# 3_DotexBoard_Interfaces.net
KiCad netlist of a schematic drawn in Altium Designer
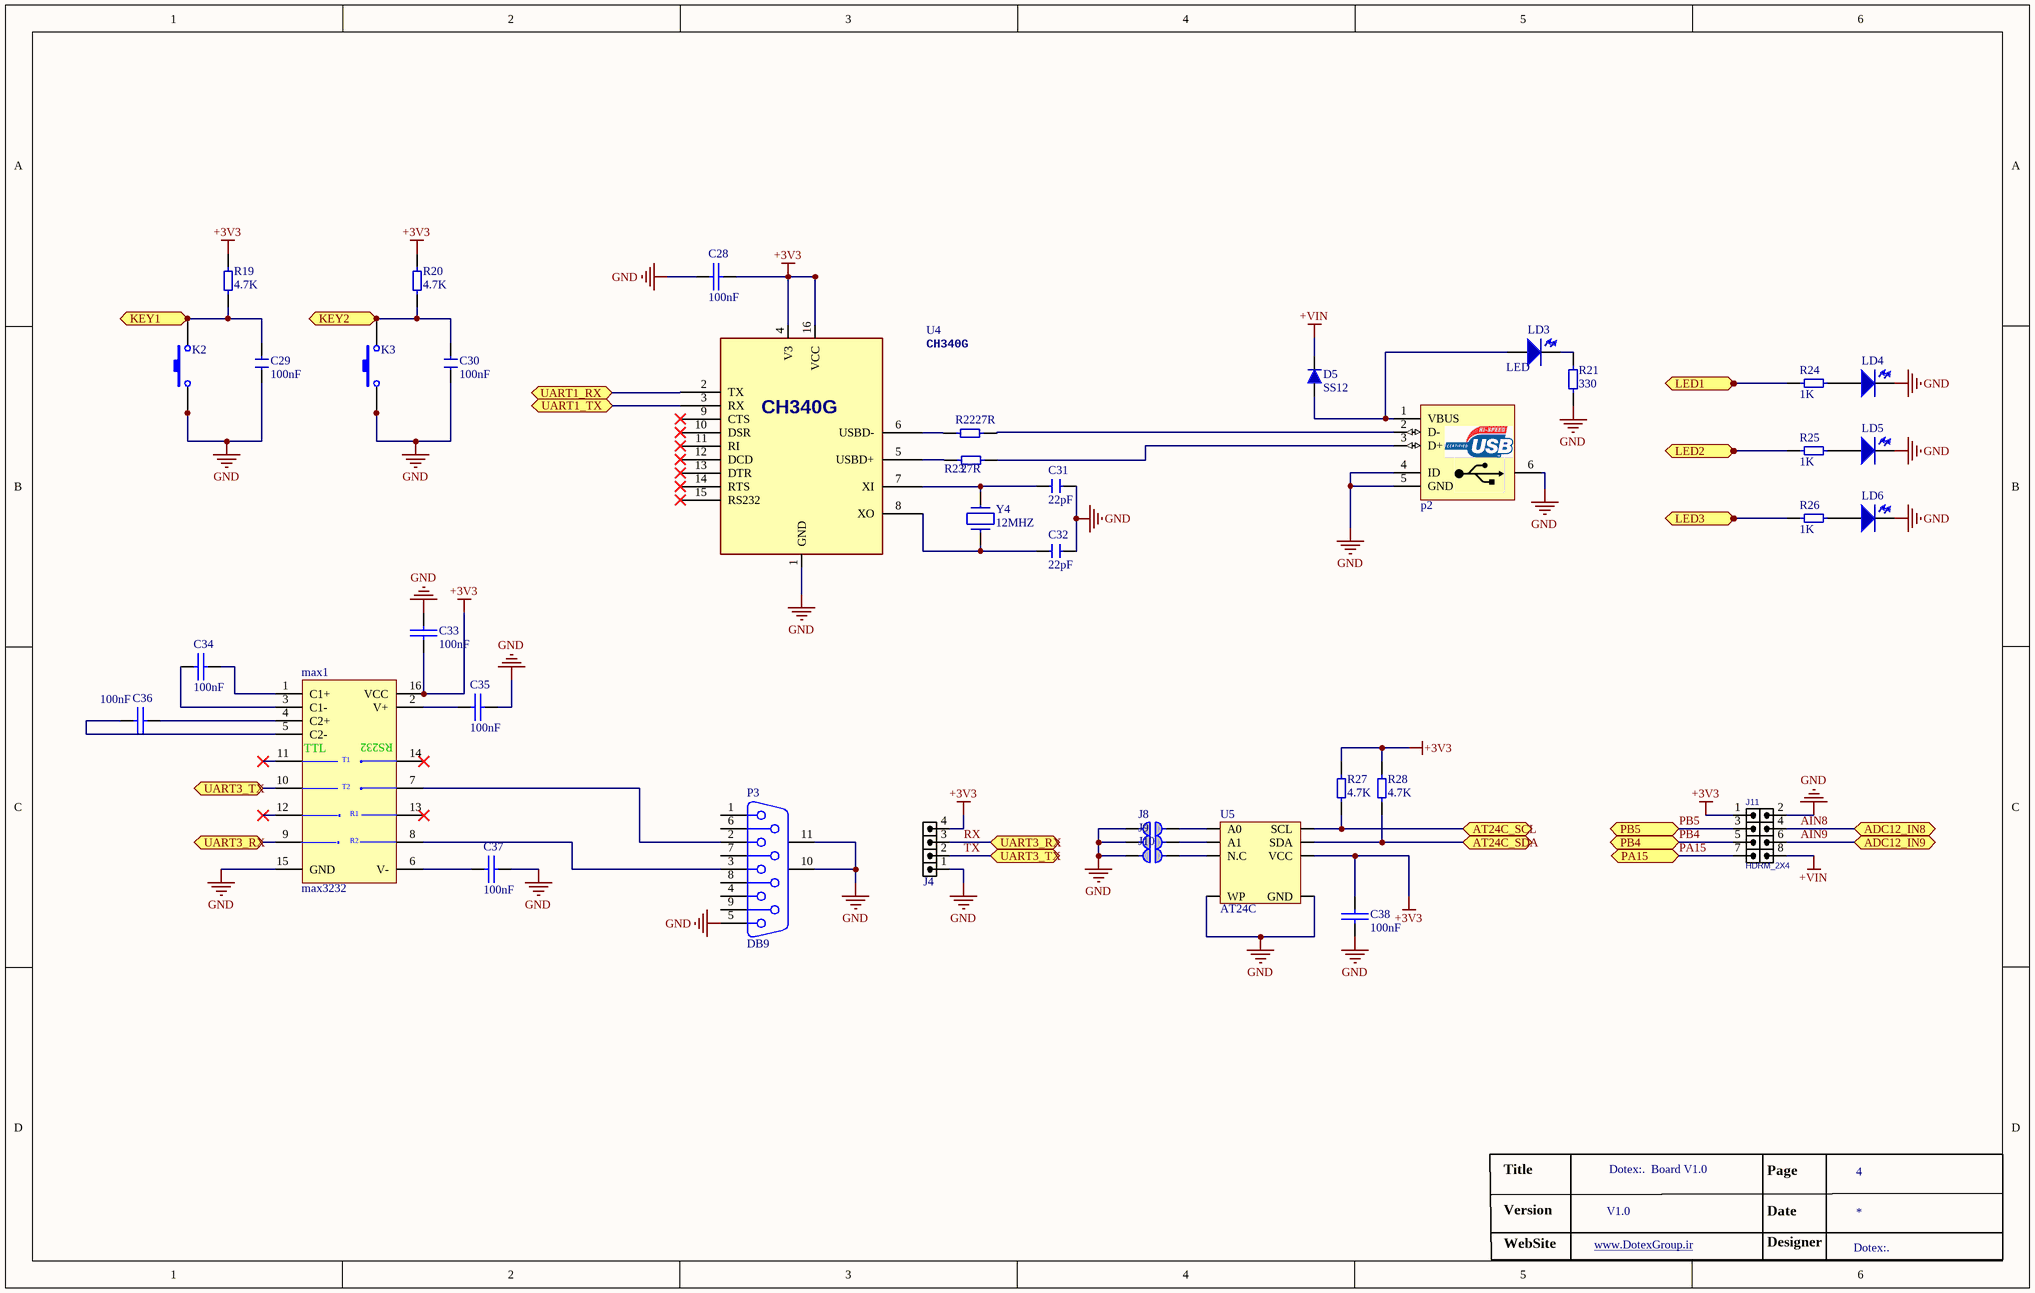
[diagram p0: [3]DotexBoard_Interfaces.SchDoc]

(export (version "E")
  (design (tool "Eeschema 10.0.6"))
  (components
    (comp (ref "C28")
      (value "100nF")
      (footprint "0805 Capacitor")
      (description "Bipolar Capacitor")
      (fields
        (field (name "VOLTAGE") "100V")
        (field (name "Comment") "Comment")
        (field (name "DESIGNER") "Saeid Jorablo")
      )
      (libsource (lib "DotexGroup_LIB") (part "Cap-Bipolar"))
    )
    (comp (ref "C29")
      (value "Comment")
      (footprint "0805 Capacitor")
      (fields (field (name "ALTIUM_UNNAMED_1") "100nF"))
      (libsource (lib "DotexGroup_LIB") (part "Capacitor SMD"))
    )
    (comp (ref "C30")
      (value "Comment")
      (footprint "0805 Capacitor")
      (fields (field (name "ALTIUM_UNNAMED_1") "100nF"))
      (libsource (lib "DotexGroup_LIB") (part "Capacitor SMD"))
    )
    (comp (ref "C31")
      (value "Comment")
      (footprint "0805 Capacitor")
      (fields (field (name "ALTIUM_UNNAMED_1") "22pF"))
      (libsource (lib "DotexGroup_LIB") (part "Capacitor SMD"))
    )
    (comp (ref "C32")
      (value "Comment")
      (footprint "0805 Capacitor")
      (fields (field (name "ALTIUM_UNNAMED_1") "22pF"))
      (libsource (lib "DotexGroup_LIB") (part "Capacitor SMD"))
    )
    (comp (ref "C33")
      (value "100nF")
      (footprint "0805 Capacitor")
      (description "Bipolar Capacitor")
      (fields
        (field (name "VOLTAGE") "100V")
        (field (name "Comment") "Comment")
        (field (name "DESIGNER") "Saeid Jorablo")
      )
      (libsource (lib "DotexGroup_LIB") (part "Cap-Bipolar"))
    )
    (comp (ref "C34")
      (value "100nF")
      (footprint "0805 Capacitor")
      (description "Bipolar Capacitor")
      (fields
        (field (name "VOLTAGE") "100V")
        (field (name "Comment") "Comment")
        (field (name "DESIGNER") "Saeid Jorablo")
      )
      (libsource (lib "DotexGroup_LIB") (part "Cap-Bipolar"))
    )
    (comp (ref "C35")
      (value "100nF")
      (footprint "0805 Capacitor")
      (description "Bipolar Capacitor")
      (fields
        (field (name "VOLTAGE") "100V")
        (field (name "Comment") "Comment")
        (field (name "DESIGNER") "Saeid Jorablo")
      )
      (libsource (lib "DotexGroup_LIB") (part "Cap-Bipolar"))
    )
    (comp (ref "C36")
      (value "100nF")
      (footprint "0805 Capacitor")
      (description "Bipolar Capacitor")
      (fields
        (field (name "VOLTAGE") "100V")
        (field (name "Comment") "Comment")
        (field (name "DESIGNER") "Saeid Jorablo")
      )
      (libsource (lib "") (part "Cap-Bipolar_1"))
    )
    (comp (ref "C37")
      (value "100nF")
      (footprint "0805 Capacitor")
      (description "Bipolar Capacitor")
      (fields
        (field (name "VOLTAGE") "100V")
        (field (name "Comment") "Comment")
        (field (name "DESIGNER") "Saeid Jorablo")
      )
      (libsource (lib "") (part "Cap-Bipolar_1"))
    )
    (comp (ref "C38")
      (value "100nF")
      (footprint "0805 Capacitor")
      (description "Bipolar Capacitor")
      (fields
        (field (name "VOLTAGE") "100V")
        (field (name "Comment") "Comment")
        (field (name "DESIGNER") "Saeid Jorablo")
      )
      (libsource (lib "") (part "Cap-Bipolar_1"))
    )
    (comp (ref "D5")
      (value "SS12")
      (footprint "DO-214AC(SMA)")
      (libsource (lib "DotexGroup_LIB") (part "1N4001"))
    )
    (comp (ref "J4")
      (value "HDR1X4")
      (footprint "HDR_M_1X4")
      (description "CONN, HEADER, Male, pitch: 2.54mm, 4POS")
      (libsource (lib "DotexGroup_LIB") (part "HDR_M_1X4"))
    )
    (comp (ref "J8")
      (value "Comment")
      (footprint "0603 Resistor")
      (libsource (lib "DotexGroup_LIB") (part "jumper SMD"))
    )
    (comp (ref "J9")
      (value "Comment")
      (footprint "0603 Resistor")
      (libsource (lib "DotexGroup_LIB") (part "jumper SMD"))
    )
    (comp (ref "J10")
      (value "Comment")
      (footprint "0603 Resistor")
      (libsource (lib "DotexGroup_LIB") (part "jumper SMD"))
    )
    (comp (ref "J11")
      (value "HDRM_2X4")
      (footprint "HDR_M_2X4")
      (description "CONN, HEADER, Male, pitch: 2.54mm, 8POS")
      (fields (field (name "MANF_P#") "MANF_PART#") (field (name "MANF") "MANF"))
      (libsource (lib "DotexGroup_LIB") (part "HDR_M_2X4"))
    )
    (comp (ref "K2")
      (value "Comment")
      (footprint "Push Kay 4 KFC")
      (libsource (lib "DotexGroup_LIB") (part "Push Kay"))
    )
    (comp (ref "K3")
      (value "Comment")
      (footprint "Push Kay 4 KFC")
      (libsource (lib "DotexGroup_LIB") (part "Push Kay"))
    )
    (comp (ref "LD3")
      (value "LED")
      (footprint "LED_0805 Y")
      (libsource (lib "DotexGroup_LIB") (part "LED SMD"))
    )
    (comp (ref "LD4")
      (value "Comment")
      (footprint "LED_0805 Y")
      (libsource (lib "DotexGroup_LIB") (part "LED SMD"))
    )
    (comp (ref "LD5")
      (value "Comment")
      (footprint "LED_0805 Y")
      (libsource (lib "DotexGroup_LIB") (part "LED SMD"))
    )
    (comp (ref "LD6")
      (value "Comment")
      (footprint "LED_0805 Y")
      (libsource (lib "DotexGroup_LIB") (part "LED SMD"))
    )
    (comp (ref "max1")
      (value "max3232")
      (footprint "SO-16")
      (description "+5V Powered, Multi-Channel RS-232 Driver/Receiver")
      (fields (field (name "COMPONENTAUTHOR") "Saeid Jorablo"))
      (libsource (lib "DotexGroup_LIB") (part "MAX232"))
    )
    (comp (ref "p2")
      (value "USB Connector")
      (footprint "USB_AB_BM_SHS")
      (description "USB MICRO-B Type Connector")
      (fields (field (name "DESIGNER") "ABBAS BASEREH") (field (name "PUBLISHER") "ABBAS BASEREH"))
      (libsource (lib "DotexGroup_LIB") (part "USB AB MICRO CONNECTOR"))
    )
    (comp (ref "P3")
      (value "DB9")
      (footprint "DB9 Female")
      (description "Receptacle Assembly, 9 Position, Right Angle")
      (fields (field (name "PUBLISHER") "Altium Limited"))
      (libsource (lib "DotexGroup_LIB") (part "DB9 Connector"))
    )
    (comp (ref "R19")
      (value "Comment")
      (footprint "0805 Resistor")
      (fields (field (name "ALTIUM_UNNAMED_1") "4.7K"))
      (libsource (lib "DotexGroup_LIB") (part "Resistor SMD"))
    )
    (comp (ref "R20")
      (value "Comment")
      (footprint "0805 Resistor")
      (fields (field (name "ALTIUM_UNNAMED_1") "4.7K"))
      (libsource (lib "DotexGroup_LIB") (part "Resistor SMD"))
    )
    (comp (ref "R21")
      (value "Comment")
      (footprint "0805 Resistor")
      (fields (field (name "ALTIUM_UNNAMED_1") "330"))
      (libsource (lib "DotexGroup_LIB") (part "Resistor SMD"))
    )
    (comp (ref "R22")
      (value "Comment")
      (footprint "0805 Resistor")
      (fields (field (name "ALTIUM_UNNAMED_1") "27R"))
      (libsource (lib "DotexGroup_LIB") (part "Resistor SMD"))
    )
    (comp (ref "R23")
      (value "Comment")
      (footprint "0805 Resistor")
      (fields (field (name "ALTIUM_UNNAMED_1") "27R"))
      (libsource (lib "DotexGroup_LIB") (part "Resistor SMD"))
    )
    (comp (ref "R24")
      (value "Comment")
      (footprint "0805 Resistor")
      (fields (field (name "ALTIUM_UNNAMED_1") "1K"))
      (libsource (lib "DotexGroup_LIB") (part "Resistor SMD"))
    )
    (comp (ref "R25")
      (value "Comment")
      (footprint "0805 Resistor")
      (fields (field (name "ALTIUM_UNNAMED_1") "1K"))
      (libsource (lib "DotexGroup_LIB") (part "Resistor SMD"))
    )
    (comp (ref "R26")
      (value "Comment")
      (footprint "0805 Resistor")
      (fields (field (name "ALTIUM_UNNAMED_1") "1K"))
      (libsource (lib "DotexGroup_LIB") (part "Resistor SMD"))
    )
    (comp (ref "R27")
      (value "Comment")
      (footprint "0805 Resistor")
      (fields (field (name "ALTIUM_UNNAMED_1") "4.7K"))
      (libsource (lib "DotexGroup_LIB") (part "Resistor SMD"))
    )
    (comp (ref "R28")
      (value "Comment")
      (footprint "0805 Resistor")
      (fields (field (name "ALTIUM_UNNAMED_1") "4.7K"))
      (libsource (lib "DotexGroup_LIB") (part "Resistor SMD"))
    )
    (comp (ref "U4")
      (value "CH340G")
      (footprint "SO-16")
      (description "USB-UART")
      (libsource (lib "DotexGroup_LIB") (part "CH340G_SOP16"))
    )
    (comp (ref "U5")
      (value "AT24C")
      (footprint "SOIC-8")
      (libsource (lib "DotexGroup_LIB") (part "AT24C128"))
    )
    (comp (ref "Y4") (value "12MHZ") (footprint "Xtal 2p") (libsource (lib "DotexGroup_LIB") (part "Xtal")))
  )
  (nets
    (net (code "1") (name "+3V3") (class "Default")
      (node (ref "C28") (pin "2") (pinfunction "-_2") (pintype "passive"))
      (node (ref "C33") (pin "1") (pinfunction "+_1") (pintype "passive"))
      (node (ref "C38") (pin "1") (pinfunction "+_1") (pintype "passive"))
      (node (ref "J11") (pin "1") (pinfunction "1_1") (pintype "passive"))
      (node (ref "J4") (pin "4") (pinfunction "4_4") (pintype "passive"))
      (node (ref "R19") (pin "1") (pintype "passive"))
      (node (ref "R20") (pin "1") (pintype "passive"))
      (node (ref "R27") (pin "1") (pintype "passive"))
      (node (ref "R28") (pin "1") (pintype "passive"))
      (node (ref "U4") (pin "16") (pinfunction "VCC_16") (pintype "passive"))
      (node (ref "U4") (pin "4") (pinfunction "V3_4") (pintype "passive"))
      (node (ref "U5") (pin "8") (pinfunction "VCC_8") (pintype "passive"))
      (node (ref "max1") (pin "16") (pinfunction "VCC_16") (pintype "power_in"))
    )
    (net (code "2") (name "+VIN") (class "Default")
      (node (ref "D5") (pin "2") (pinfunction "K_2") (pintype "passive"))
      (node (ref "J11") (pin "8") (pinfunction "8_8") (pintype "passive"))
    )
    (net (code "3") (name "/AIN8") (class "Default")
      (node (ref "J11") (pin "4") (pinfunction "4_4") (pintype "passive"))
    )
    (net (code "4") (name "/AIN9") (class "Default")
      (node (ref "J11") (pin "6") (pinfunction "6_6") (pintype "passive"))
    )
    (net (code "5") (name "/AT24C_SCL") (class "Default")
      (node (ref "R27") (pin "2") (pintype "passive"))
      (node (ref "U5") (pin "6") (pinfunction "SCL_6") (pintype "passive"))
    )
    (net (code "6") (name "/AT24C_SDA") (class "Default")
      (node (ref "R28") (pin "2") (pintype "passive"))
      (node (ref "U5") (pin "5") (pinfunction "SDA_5") (pintype "passive"))
    )
    (net (code "7") (name "/KEY1") (class "Default")
      (node (ref "C29") (pin "1") (pintype "passive"))
      (node (ref "K2") (pin "2") (pinfunction "2_2") (pintype "passive"))
      (node (ref "R19") (pin "2") (pintype "passive"))
    )
    (net (code "8") (name "/KEY2") (class "Default")
      (node (ref "C30") (pin "1") (pintype "passive"))
      (node (ref "K3") (pin "2") (pinfunction "2_2") (pintype "passive"))
      (node (ref "R20") (pin "2") (pintype "passive"))
    )
    (net (code "9") (name "/LED1") (class "Default") (node (ref "R24") (pin "1") (pintype "passive")))
    (net (code "10") (name "/LED2") (class "Default") (node (ref "R25") (pin "1") (pintype "passive")))
    (net (code "11") (name "/LED3") (class "Default") (node (ref "R26") (pin "1") (pintype "passive")))
    (net (code "12") (name "/PA15") (class "Default")
      (node (ref "J11") (pin "7") (pinfunction "7_7") (pintype "passive"))
    )
    (net (code "13") (name "/PB4") (class "Default")
      (node (ref "J11") (pin "5") (pinfunction "5_5") (pintype "passive"))
    )
    (net (code "14") (name "/PB5") (class "Default")
      (node (ref "J11") (pin "3") (pinfunction "3_3") (pintype "passive"))
    )
    (net (code "15") (name "/RX") (class "Default")
      (node (ref "J4") (pin "3") (pinfunction "3_3") (pintype "passive"))
      (node (ref "max1") (pin "9") (pinfunction "R2OUT_9") (pintype "passive"))
    )
    (net (code "16") (name "/TX") (class "Default")
      (node (ref "J4") (pin "2") (pinfunction "2_2") (pintype "passive"))
      (node (ref "max1") (pin "10") (pinfunction "T2IN_10") (pintype "passive"))
    )
    (net (code "17") (name "/UART1_RX") (class "Default")
      (node (ref "U4") (pin "2") (pinfunction "TX_2") (pintype "passive"))
    )
    (net (code "18") (name "/UART1_TX") (class "Default")
      (node (ref "U4") (pin "3") (pinfunction "RX_3") (pintype "passive"))
    )
    (net (code "19") (name "GND") (class "Default")
      (node (ref "C28") (pin "1") (pinfunction "+_1") (pintype "passive"))
      (node (ref "C29") (pin "2") (pintype "passive"))
      (node (ref "C30") (pin "2") (pintype "passive"))
      (node (ref "C31") (pin "1") (pintype "passive"))
      (node (ref "C32") (pin "2") (pintype "passive"))
      (node (ref "C33") (pin "2") (pinfunction "-_2") (pintype "passive"))
      (node (ref "C35") (pin "2") (pinfunction "-_2") (pintype "passive"))
      (node (ref "C37") (pin "2") (pinfunction "-_2") (pintype "passive"))
      (node (ref "C38") (pin "2") (pinfunction "-_2") (pintype "passive"))
      (node (ref "J10") (pin "1") (pintype "passive"))
      (node (ref "J11") (pin "2") (pinfunction "2_2") (pintype "passive"))
      (node (ref "J4") (pin "1") (pinfunction "1_1") (pintype "passive"))
      (node (ref "J8") (pin "1") (pintype "passive"))
      (node (ref "J9") (pin "1") (pintype "passive"))
      (node (ref "K2") (pin "1") (pinfunction "1_1") (pintype "passive"))
      (node (ref "K3") (pin "1") (pinfunction "1_1") (pintype "passive"))
      (node (ref "LD4") (pin "2") (pinfunction "K_2") (pintype "passive"))
      (node (ref "LD5") (pin "2") (pinfunction "K_2") (pintype "passive"))
      (node (ref "LD6") (pin "2") (pinfunction "K_2") (pintype "passive"))
      (node (ref "P3") (pin "10") (pinfunction "MH1_10") (pintype "passive"))
      (node (ref "P3") (pin "11") (pinfunction "MH2_11") (pintype "passive"))
      (node (ref "P3") (pin "5") (pinfunction "5_5") (pintype "passive"))
      (node (ref "R21") (pin "2") (pintype "passive"))
      (node (ref "U4") (pin "1") (pinfunction "GND_1") (pintype "passive"))
      (node (ref "U5") (pin "4") (pinfunction "GND_4") (pintype "passive"))
      (node (ref "U5") (pin "7") (pinfunction "WP_7") (pintype "passive"))
      (node (ref "max1") (pin "15") (pinfunction "GND_15") (pintype "power_in"))
      (node (ref "p2") (pin "4") (pinfunction "ID_4") (pintype "power_in"))
      (node (ref "p2") (pin "5") (pinfunction "GND_5") (pintype "power_in"))
      (node (ref "p2") (pin "6") (pinfunction "MH_6") (pintype "power_in"))
    )
    (net (code "20") (name "Net-(C34-+)") (class "Default")
      (node (ref "C34") (pin "1") (pinfunction "+_1") (pintype "passive"))
      (node (ref "max1") (pin "1") (pinfunction "C1+_1") (pintype "passive"))
    )
    (net (code "21") (name "Net-(C34--)") (class "Default")
      (node (ref "C34") (pin "2") (pinfunction "-_2") (pintype "passive"))
      (node (ref "max1") (pin "3") (pinfunction "C1-_3") (pintype "passive"))
    )
    (net (code "22") (name "Net-(C35-+)") (class "Default")
      (node (ref "C35") (pin "1") (pinfunction "+_1") (pintype "passive"))
      (node (ref "max1") (pin "2") (pinfunction "V+_2") (pintype "passive"))
    )
    (net (code "23") (name "Net-(C36-+)") (class "Default")
      (node (ref "C36") (pin "1") (pinfunction "+_1") (pintype "passive"))
      (node (ref "max1") (pin "5") (pinfunction "C2-_5") (pintype "passive"))
    )
    (net (code "24") (name "Net-(C36--)") (class "Default")
      (node (ref "C36") (pin "2") (pinfunction "-_2") (pintype "passive"))
      (node (ref "max1") (pin "4") (pinfunction "C2+_4") (pintype "passive"))
    )
    (net (code "25") (name "Net-(C37-+)") (class "Default")
      (node (ref "C37") (pin "1") (pinfunction "+_1") (pintype "passive"))
      (node (ref "max1") (pin "6") (pinfunction "V-_6") (pintype "passive"))
    )
    (net (code "26") (name "Net-(D5-A)") (class "Default")
      (node (ref "D5") (pin "1") (pinfunction "A_1") (pintype "passive"))
      (node (ref "LD3") (pin "1") (pinfunction "A_1") (pintype "passive"))
      (node (ref "p2") (pin "1") (pinfunction "VBUS_1") (pintype "power_in"))
    )
    (net (code "27") (name "Net-(LD3-K)") (class "Default")
      (node (ref "LD3") (pin "2") (pinfunction "K_2") (pintype "passive"))
      (node (ref "R21") (pin "1") (pintype "passive"))
    )
    (net (code "28") (name "Net-(LD4-A)") (class "Default")
      (node (ref "LD4") (pin "1") (pinfunction "A_1") (pintype "passive"))
      (node (ref "R24") (pin "2") (pintype "passive"))
    )
    (net (code "29") (name "Net-(LD5-A)") (class "Default")
      (node (ref "LD5") (pin "1") (pinfunction "A_1") (pintype "passive"))
      (node (ref "R25") (pin "2") (pintype "passive"))
    )
    (net (code "30") (name "Net-(LD6-A)") (class "Default")
      (node (ref "LD6") (pin "1") (pinfunction "A_1") (pintype "passive"))
      (node (ref "R26") (pin "2") (pintype "passive"))
    )
    (net (code "31") (name "Net-(U4-USBD+)") (class "Default")
      (node (ref "R23") (pin "1") (pintype "passive"))
      (node (ref "U4") (pin "5") (pinfunction "USBD+_5") (pintype "passive"))
    )
    (net (code "32") (name "Net-(U4-USBD-)") (class "Default")
      (node (ref "R22") (pin "1") (pintype "passive"))
      (node (ref "U4") (pin "6") (pinfunction "USBD-_6") (pintype "passive"))
    )
    (net (code "33") (name "Net-(U4-XI)") (class "Default")
      (node (ref "C31") (pin "2") (pintype "passive"))
      (node (ref "U4") (pin "7") (pinfunction "XI_7") (pintype "passive"))
      (node (ref "Y4") (pin "2") (pintype "passive"))
    )
    (net (code "34") (name "Net-(U4-XO)") (class "Default")
      (node (ref "C32") (pin "1") (pintype "passive"))
      (node (ref "U4") (pin "8") (pinfunction "XO_8") (pintype "passive"))
      (node (ref "Y4") (pin "1") (pintype "passive"))
    )
    (net (code "35") (name "Net-(U5-A0)") (class "Default")
      (node (ref "J8") (pin "2") (pintype "passive"))
      (node (ref "U5") (pin "1") (pinfunction "A0_1") (pintype "passive"))
    )
    (net (code "36") (name "Net-(U5-A1)") (class "Default")
      (node (ref "J9") (pin "2") (pintype "passive"))
      (node (ref "U5") (pin "2") (pinfunction "A1_2") (pintype "passive"))
    )
    (net (code "37") (name "Net-(U5-N.C)") (class "Default")
      (node (ref "J10") (pin "2") (pintype "passive"))
      (node (ref "U5") (pin "3") (pinfunction "N.C_3") (pintype "passive"))
    )
    (net (code "38") (name "Net-(max1-R2IN)") (class "Default")
      (node (ref "P3") (pin "3") (pinfunction "3_3") (pintype "passive"))
      (node (ref "max1") (pin "8") (pinfunction "R2IN_8") (pintype "passive"))
    )
    (net (code "39") (name "Net-(max1-T2OUT)") (class "Default")
      (node (ref "P3") (pin "2") (pinfunction "2_2") (pintype "passive"))
      (node (ref "max1") (pin "7") (pinfunction "T2OUT_7") (pintype "passive"))
    )
    (net (code "40") (name "Net-(p2-D+)") (class "Default")
      (node (ref "R23") (pin "2") (pintype "passive"))
      (node (ref "p2") (pin "3") (pinfunction "D+_3") (pintype "bidirectional"))
    )
    (net (code "41") (name "Net-(p2-D-)") (class "Default")
      (node (ref "R22") (pin "2") (pintype "passive"))
      (node (ref "p2") (pin "2") (pinfunction "D-_2") (pintype "bidirectional"))
    )
    (net (code "42") (name "unconnected-(P3-Pad1)") (class "Default")
      (node (ref "P3") (pin "1") (pinfunction "1_1") (pintype "passive"))
    )
    (net (code "43") (name "unconnected-(P3-Pad4)") (class "Default")
      (node (ref "P3") (pin "4") (pinfunction "4_4") (pintype "passive"))
    )
    (net (code "44") (name "unconnected-(P3-Pad6)") (class "Default")
      (node (ref "P3") (pin "6") (pinfunction "6_6") (pintype "passive"))
    )
    (net (code "45") (name "unconnected-(P3-Pad7)") (class "Default")
      (node (ref "P3") (pin "7") (pinfunction "7_7") (pintype "passive"))
    )
    (net (code "46") (name "unconnected-(P3-Pad8)") (class "Default")
      (node (ref "P3") (pin "8") (pinfunction "8_8") (pintype "passive"))
    )
    (net (code "47") (name "unconnected-(P3-Pad9)") (class "Default")
      (node (ref "P3") (pin "9") (pinfunction "9_9") (pintype "passive"))
    )
    (net (code "48") (name "unconnected-(U4-CTS-Pad9)") (class "Default")
      (node (ref "U4") (pin "9") (pinfunction "CTS_9") (pintype "passive+no_connect"))
    )
    (net (code "49") (name "unconnected-(U4-DCD-Pad12)") (class "Default")
      (node (ref "U4") (pin "12") (pinfunction "DCD_12") (pintype "passive+no_connect"))
    )
    (net (code "50") (name "unconnected-(U4-DSR-Pad10)") (class "Default")
      (node (ref "U4") (pin "10") (pinfunction "DSR_10") (pintype "passive+no_connect"))
    )
    (net (code "51") (name "unconnected-(U4-DTR-Pad13)") (class "Default")
      (node (ref "U4") (pin "13") (pinfunction "DTR_13") (pintype "passive+no_connect"))
    )
    (net (code "52") (name "unconnected-(U4-RI-Pad11)") (class "Default")
      (node (ref "U4") (pin "11") (pinfunction "RI_11") (pintype "passive+no_connect"))
    )
    (net (code "53") (name "unconnected-(U4-RS232-Pad15)") (class "Default")
      (node (ref "U4") (pin "15") (pinfunction "RS232_15") (pintype "passive+no_connect"))
    )
    (net (code "54") (name "unconnected-(U4-RTS-Pad14)") (class "Default")
      (node (ref "U4") (pin "14") (pinfunction "RTS_14") (pintype "passive+no_connect"))
    )
    (net (code "55") (name "unconnected-(max1-R1IN-Pad13)") (class "Default")
      (node (ref "max1") (pin "13") (pinfunction "R1IN_13") (pintype "passive+no_connect"))
    )
    (net (code "56") (name "unconnected-(max1-R1OUT-Pad12)") (class "Default")
      (node (ref "max1") (pin "12") (pinfunction "R1OUT_12") (pintype "passive+no_connect"))
    )
    (net (code "57") (name "unconnected-(max1-T1IN-Pad11)") (class "Default")
      (node (ref "max1") (pin "11") (pinfunction "T1IN_11") (pintype "passive+no_connect"))
    )
    (net (code "58") (name "unconnected-(max1-T1OUT-Pad14)") (class "Default")
      (node (ref "max1") (pin "14") (pinfunction "T1OUT_14") (pintype "passive+no_connect"))
    )
  )
)
